# User_Interface.net
KiCad netlist of a schematic drawn in Altium Designer
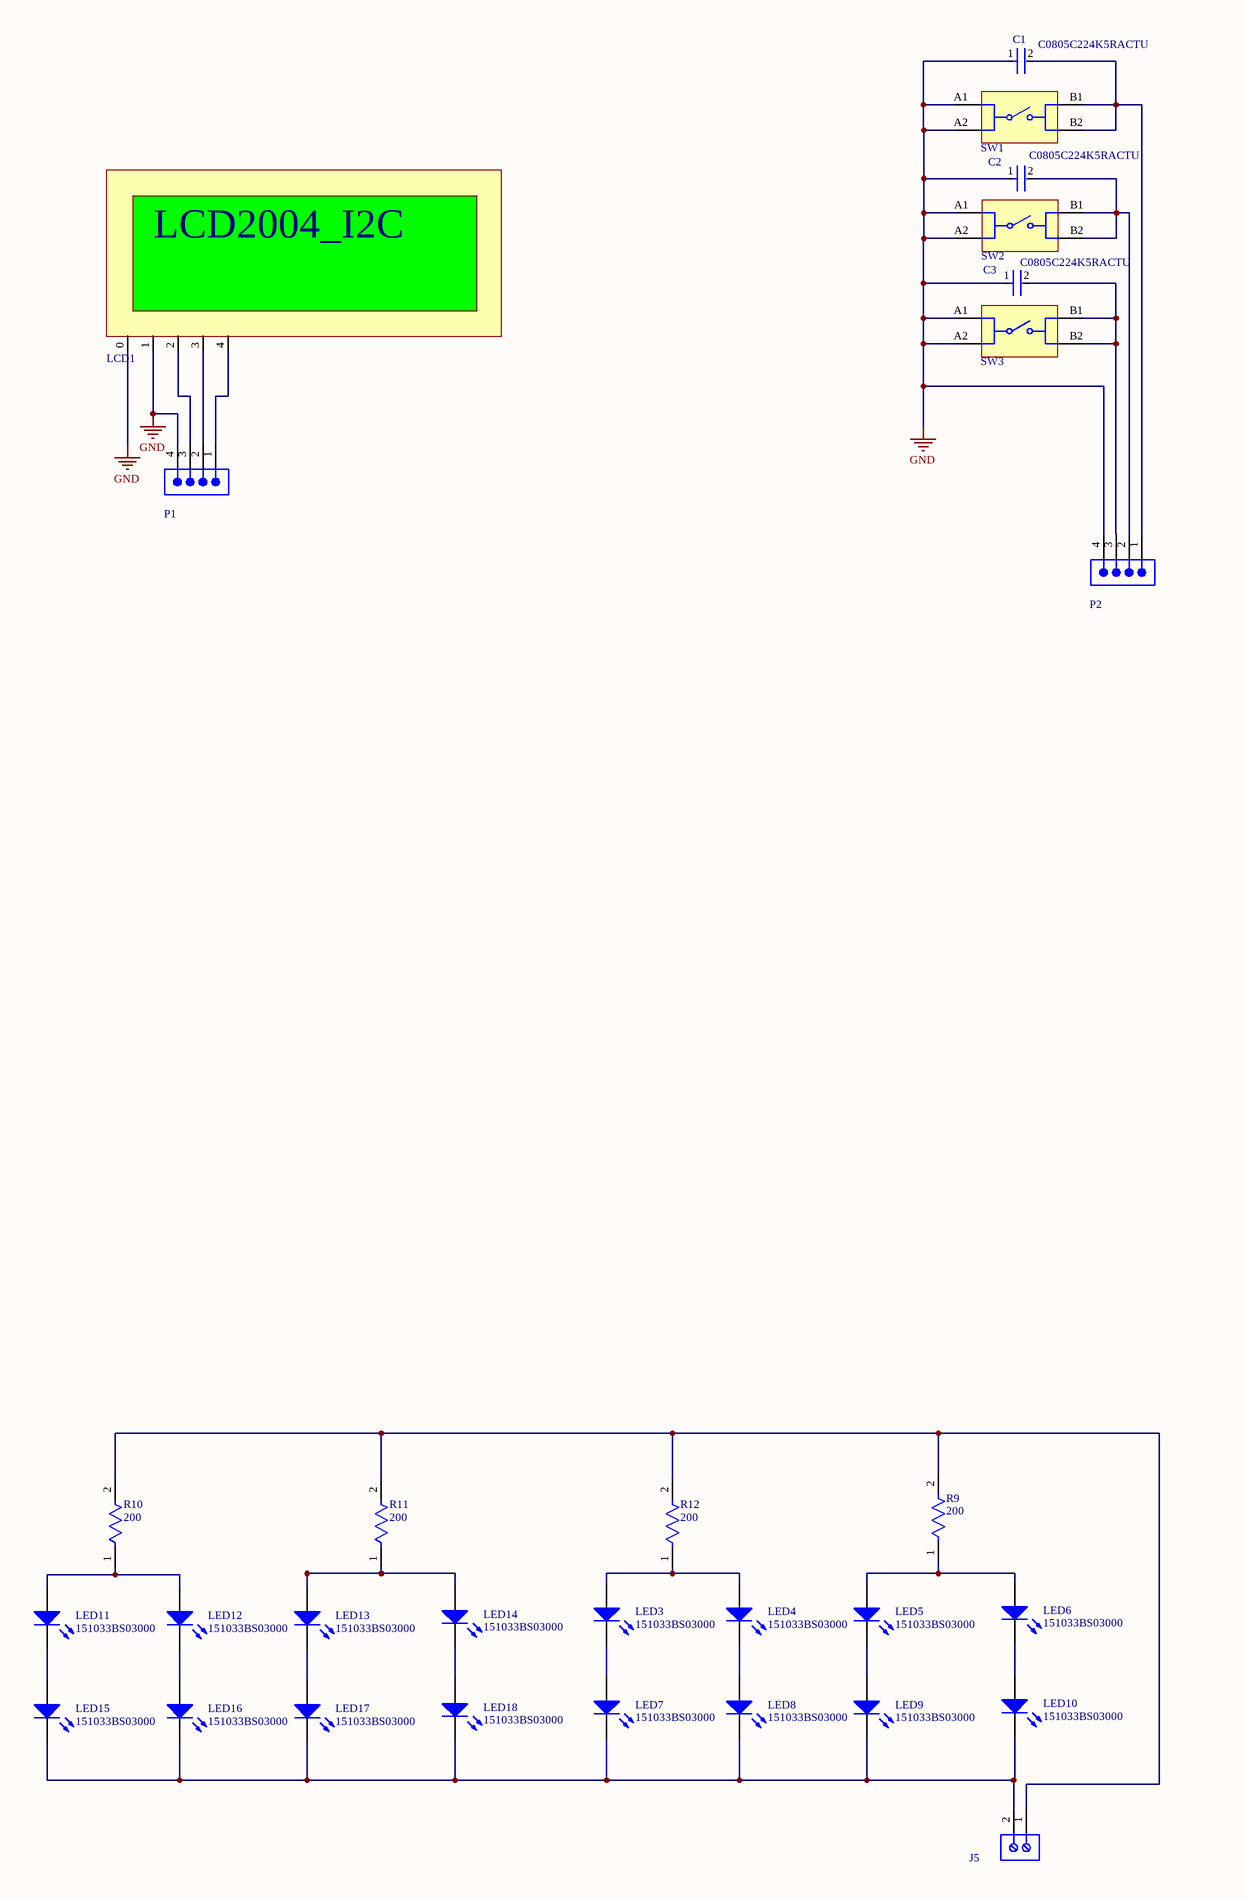
[diagram p0: User_Interface.SchDoc, left]
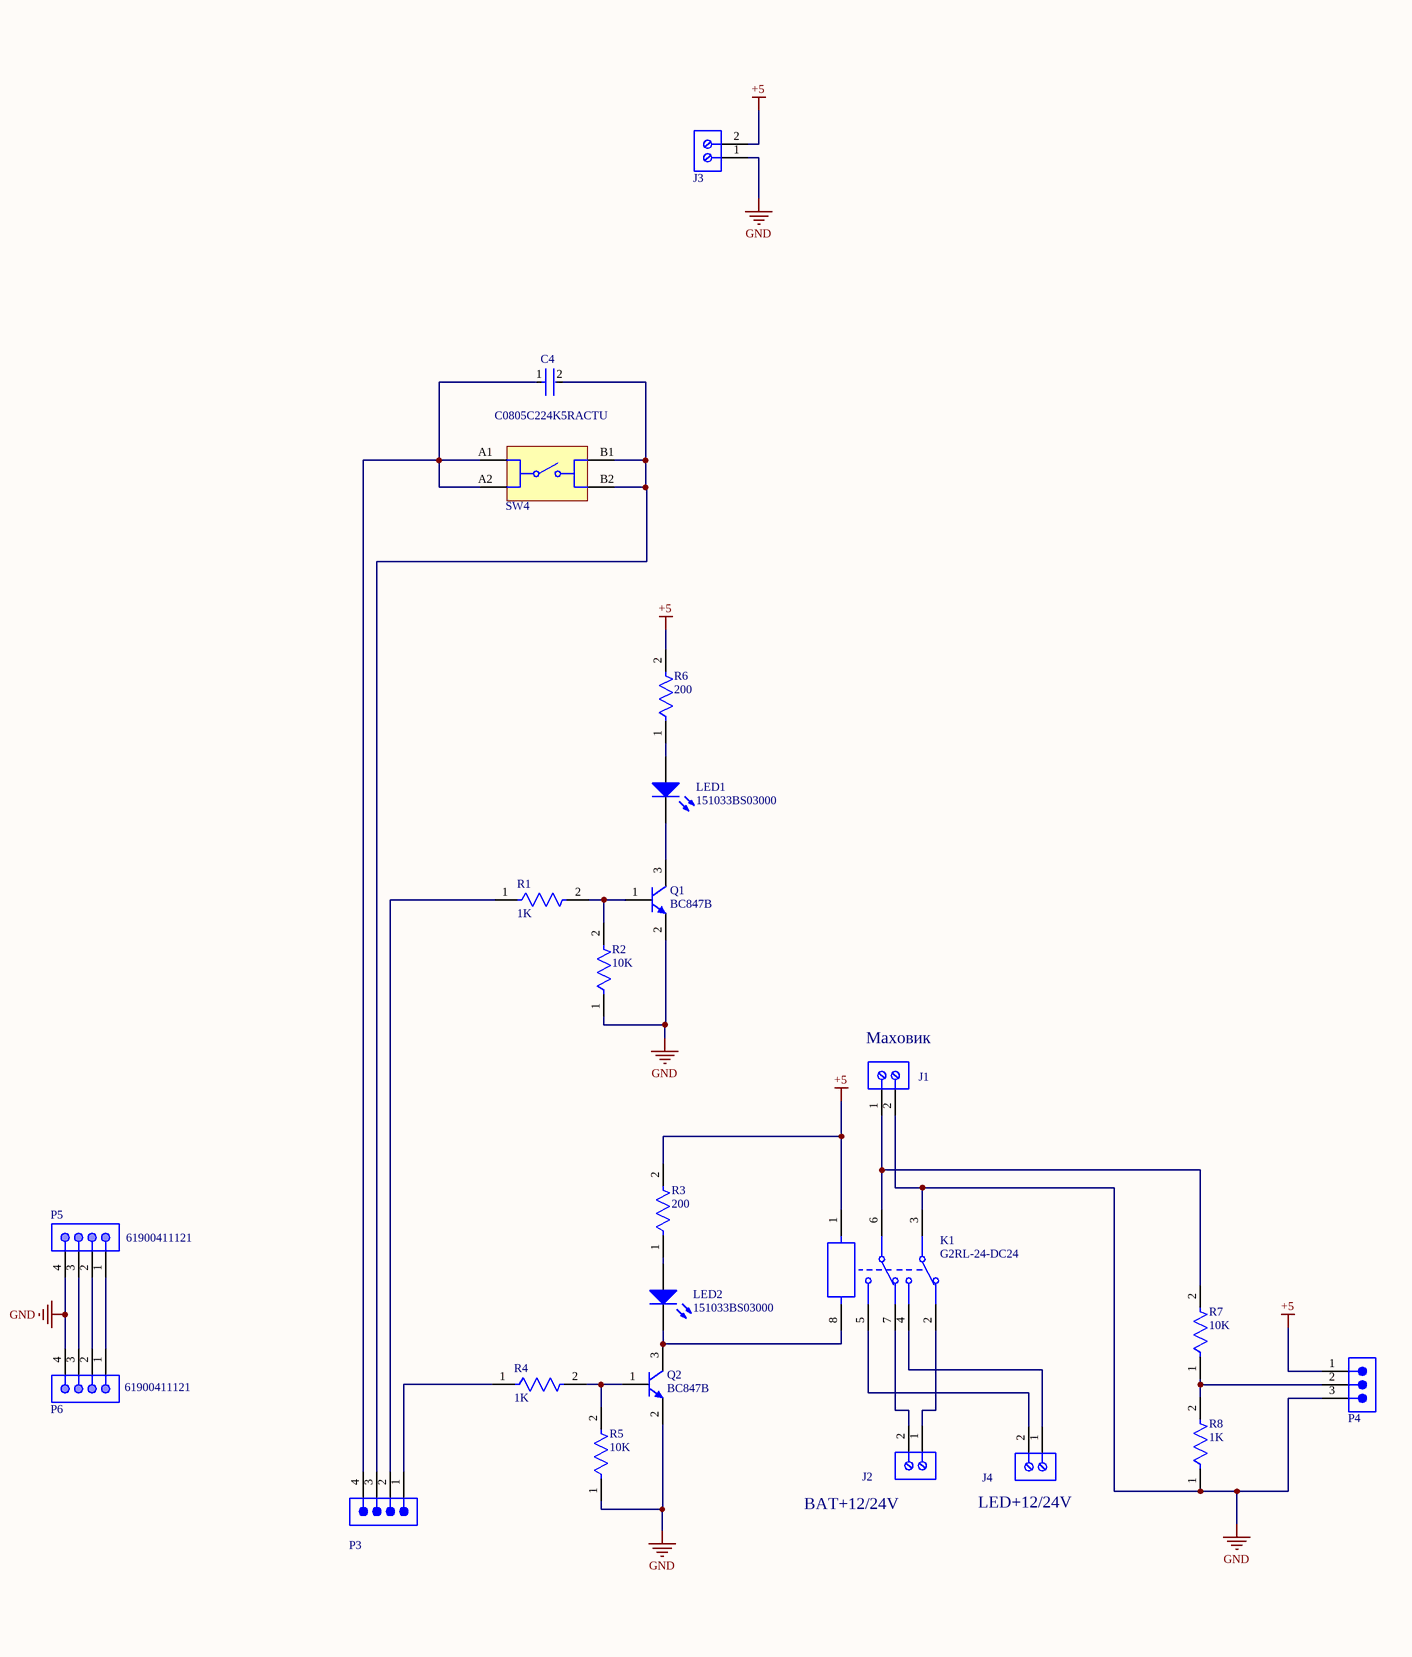
[diagram p1: User_Interface.SchDoc, right]

(export (version "E")
  (design (tool "Eeschema 10.0.6"))
  (components
    (comp (ref "C1")
      (value "C0805C224K5RACTU")
      (footprint "FP-C0805C-DN-IPC_A")
      (description "CAP CER 0.22UF 50V X7R 0805")
      (fields
        (field (name "MANUFACTURER") "KEMET")
        (field (name "OCTOPART") "https://octopart.com/c0805c224k5ractu-kemet-144670")
      )
      (libsource (lib "Pasive_components") (part "CMP-1036-04552-2"))
    )
    (comp (ref "C2")
      (value "C0805C224K5RACTU")
      (footprint "FP-C0805C-DN-IPC_A")
      (description "CAP CER 0.22UF 50V X7R 0805")
      (fields
        (field (name "MANUFACTURER") "KEMET")
        (field (name "OCTOPART") "https://octopart.com/c0805c224k5ractu-kemet-144670")
      )
      (libsource (lib "Pasive_components") (part "CMP-1036-04552-2"))
    )
    (comp (ref "C3")
      (value "C0805C224K5RACTU")
      (footprint "FP-C0805C-DN-IPC_A")
      (description "CAP CER 0.22UF 50V X7R 0805")
      (fields
        (field (name "MANUFACTURER") "KEMET")
        (field (name "OCTOPART") "https://octopart.com/c0805c224k5ractu-kemet-144670")
      )
      (libsource (lib "Pasive_components") (part "CMP-1036-04552-2"))
    )
    (comp (ref "C4")
      (value "C0805C224K5RACTU")
      (footprint "FP-C0805C-DN-IPC_A")
      (description "CAP CER 0.22UF 50V X7R 0805")
      (fields
        (field (name "MANUFACTURER") "KEMET")
        (field (name "OCTOPART") "https://octopart.com/c0805c224k5ractu-kemet-144670")
      )
      (libsource (lib "Pasive_components") (part "CMP-1036-04552-2"))
    )
    (comp (ref "J1")
      (value "691101710002")
      (footprint "691101710002")
      (description "WR-TBL Series 101 Horizontal Entry Modular, THT, pitch 5mm, 2p")
      (fields (field (name "MANUFACTURER") "Wurth Elektronik"))
      (libsource (lib "Altium_WR-TBL (rev23a)") (part "691101710002"))
    )
    (comp (ref "J2")
      (value "691101710002")
      (footprint "691101710002")
      (description "WR-TBL Series 101 Horizontal Entry Modular, THT, pitch 5mm, 2p")
      (fields (field (name "MANUFACTURER") "Wurth Elektronik"))
      (libsource (lib "Altium_WR-TBL (rev23a)") (part "691101710002"))
    )
    (comp (ref "J3")
      (value "691101710002")
      (footprint "691101710002")
      (description "WR-TBL Series 101 Horizontal Entry Modular, THT, pitch 5mm, 2p")
      (fields (field (name "MANUFACTURER") "Wurth Elektronik"))
      (libsource (lib "Altium_WR-TBL (rev23a)") (part "691101710002"))
    )
    (comp (ref "J4")
      (value "691101710002")
      (footprint "691101710002")
      (description "WR-TBL Series 101 Horizontal Entry Modular, THT, pitch 5mm, 2p")
      (fields (field (name "MANUFACTURER") "Wurth Elektronik"))
      (libsource (lib "Altium_WR-TBL (rev23a)") (part "691101710002"))
    )
    (comp (ref "J5")
      (value "691101710002")
      (footprint "691101710002")
      (description "WR-TBL Series 101 Horizontal Entry Modular, THT, pitch 5mm, 2p")
      (fields (field (name "MANUFACTURER") "Wurth Elektronik"))
      (libsource (lib "Altium_WR-TBL (rev23a)") (part "691101710002"))
    )
    (comp (ref "K1")
      (value "G2RL-24-DC24")
      (footprint "OMRON-G2RL-24_V")
      (fields (field (name "MANUFACTURER") "Omron"))
      (libsource (lib "Altium Content Vault") (part "RELAY-DPDT-8_C"))
    )
    (comp (ref "LCD1")
      (value "2004_I2C")
      (footprint "LCD2004_I2C")
      (libsource (lib "LCD2004_I2C") (part "LCD2004_I2C"))
    )
    (comp (ref "LED1")
      (value "151033BS03000")
      (footprint "Type 3mm")
      (description "THT LED round mono-color waterclear, WL-TMRW , Blue")
      (fields (field (name "MANUFACTURER") "Wuerth Elektronik"))
      (libsource (lib "Optic-LED") (part "151033BS03000"))
    )
    (comp (ref "LED2")
      (value "151033BS03000")
      (footprint "Type 3mm")
      (description "THT LED round mono-color waterclear, WL-TMRW , Blue")
      (fields (field (name "MANUFACTURER") "Wuerth Elektronik"))
      (libsource (lib "Optic-LED") (part "151033BS03000"))
    )
    (comp (ref "LED3")
      (value "151033BS03000")
      (footprint "Type 3mm")
      (description "THT LED round mono-color waterclear, WL-TMRW , Blue")
      (fields (field (name "MANUFACTURER") "Wuerth Elektronik"))
      (libsource (lib "Optic-LED") (part "151033BS03000"))
    )
    (comp (ref "LED4")
      (value "151033BS03000")
      (footprint "Type 3mm")
      (description "THT LED round mono-color waterclear, WL-TMRW , Blue")
      (fields (field (name "MANUFACTURER") "Wuerth Elektronik"))
      (libsource (lib "Optic-LED") (part "151033BS03000"))
    )
    (comp (ref "LED5")
      (value "151033BS03000")
      (footprint "Type 3mm")
      (description "THT LED round mono-color waterclear, WL-TMRW , Blue")
      (fields (field (name "MANUFACTURER") "Wuerth Elektronik"))
      (libsource (lib "Optic-LED") (part "151033BS03000"))
    )
    (comp (ref "LED6")
      (value "151033BS03000")
      (footprint "Type 3mm")
      (description "THT LED round mono-color waterclear, WL-TMRW , Blue")
      (fields (field (name "MANUFACTURER") "Wuerth Elektronik"))
      (libsource (lib "Optic-LED") (part "151033BS03000"))
    )
    (comp (ref "LED7")
      (value "151033BS03000")
      (footprint "Type 3mm")
      (description "THT LED round mono-color waterclear, WL-TMRW , Blue")
      (fields (field (name "MANUFACTURER") "Wuerth Elektronik"))
      (libsource (lib "Optic-LED") (part "151033BS03000"))
    )
    (comp (ref "LED8")
      (value "151033BS03000")
      (footprint "Type 3mm")
      (description "THT LED round mono-color waterclear, WL-TMRW , Blue")
      (fields (field (name "MANUFACTURER") "Wuerth Elektronik"))
      (libsource (lib "Optic-LED") (part "151033BS03000"))
    )
    (comp (ref "LED9")
      (value "151033BS03000")
      (footprint "Type 3mm")
      (description "THT LED round mono-color waterclear, WL-TMRW , Blue")
      (fields (field (name "MANUFACTURER") "Wuerth Elektronik"))
      (libsource (lib "Optic-LED") (part "151033BS03000"))
    )
    (comp (ref "LED10")
      (value "151033BS03000")
      (footprint "Type 3mm")
      (description "THT LED round mono-color waterclear, WL-TMRW , Blue")
      (fields (field (name "MANUFACTURER") "Wuerth Elektronik"))
      (libsource (lib "Optic-LED") (part "151033BS03000"))
    )
    (comp (ref "LED11")
      (value "151033BS03000")
      (footprint "Type 3mm")
      (description "THT LED round mono-color waterclear, WL-TMRW , Blue")
      (fields (field (name "MANUFACTURER") "Wuerth Elektronik"))
      (libsource (lib "Optic-LED") (part "151033BS03000"))
    )
    (comp (ref "LED12")
      (value "151033BS03000")
      (footprint "Type 3mm")
      (description "THT LED round mono-color waterclear, WL-TMRW , Blue")
      (fields (field (name "MANUFACTURER") "Wuerth Elektronik"))
      (libsource (lib "Optic-LED") (part "151033BS03000"))
    )
    (comp (ref "LED13")
      (value "151033BS03000")
      (footprint "Type 3mm")
      (description "THT LED round mono-color waterclear, WL-TMRW , Blue")
      (fields (field (name "MANUFACTURER") "Wuerth Elektronik"))
      (libsource (lib "Optic-LED") (part "151033BS03000"))
    )
    (comp (ref "LED14")
      (value "151033BS03000")
      (footprint "Type 3mm")
      (description "THT LED round mono-color waterclear, WL-TMRW , Blue")
      (fields (field (name "MANUFACTURER") "Wuerth Elektronik"))
      (libsource (lib "Optic-LED") (part "151033BS03000"))
    )
    (comp (ref "LED15")
      (value "151033BS03000")
      (footprint "Type 3mm")
      (description "THT LED round mono-color waterclear, WL-TMRW , Blue")
      (fields (field (name "MANUFACTURER") "Wuerth Elektronik"))
      (libsource (lib "Optic-LED") (part "151033BS03000"))
    )
    (comp (ref "LED16")
      (value "151033BS03000")
      (footprint "Type 3mm")
      (description "THT LED round mono-color waterclear, WL-TMRW , Blue")
      (fields (field (name "MANUFACTURER") "Wuerth Elektronik"))
      (libsource (lib "Optic-LED") (part "151033BS03000"))
    )
    (comp (ref "LED17")
      (value "151033BS03000")
      (footprint "Type 3mm")
      (description "THT LED round mono-color waterclear, WL-TMRW , Blue")
      (fields (field (name "MANUFACTURER") "Wuerth Elektronik"))
      (libsource (lib "Optic-LED") (part "151033BS03000"))
    )
    (comp (ref "LED18")
      (value "151033BS03000")
      (footprint "Type 3mm")
      (description "THT LED round mono-color waterclear, WL-TMRW , Blue")
      (fields (field (name "MANUFACTURER") "Wuerth Elektronik"))
      (libsource (lib "Optic-LED") (part "151033BS03000"))
    )
    (comp (ref "P1")
      (value "61900411121")
      (footprint "61900411121")
      (description "WR-WTB THT Male Vertical Locking Header, pitch 2.54mm, 4pins")
      (fields (field (name "MANUFACTURER") "Wurth Elektronik"))
      (libsource (lib "Altium_WR-WTB (rev22b)") (part "61900411121"))
    )
    (comp (ref "P2")
      (value "61900411121")
      (footprint "61900411121")
      (description "WR-WTB THT Male Vertical Locking Header, pitch 2.54mm, 4pins")
      (fields (field (name "MANUFACTURER") "Wurth Elektronik"))
      (libsource (lib "Altium_WR-WTB (rev22b)") (part "61900411121"))
    )
    (comp (ref "P3")
      (value "61900411121")
      (footprint "61900411121")
      (description "WR-WTB THT Male Vertical Locking Header, pitch 2.54mm, 4pins")
      (fields (field (name "MANUFACTURER") "Wurth Elektronik"))
      (libsource (lib "Altium_WR-WTB (rev22b)") (part "61900411121"))
    )
    (comp (ref "P4")
      (value "61900311121")
      (footprint "61900311121")
      (description "WR-WTB THT Male Vertical Locking Header, pitch 2.54mm, 3pins")
      (fields (field (name "MANUFACTURER") "Wurth Elektronik"))
      (libsource (lib "Altium_WR-WTB (rev22b)") (part "61900311121"))
    )
    (comp (ref "P5")
      (value "61900411121")
      (footprint "61900411121")
      (description "WR-WTB THT Male Vertical Locking Header, pitch 2.54mm, 4p")
      (fields (field (name "PUBLISHER") "Wurth Elektronik"))
      (libsource (lib "Altium_WR-WTB (rev20a)") (part "61900411121"))
    )
    (comp (ref "P6")
      (value "61900411121")
      (footprint "61900411121")
      (description "WR-WTB THT Male Vertical Locking Header, pitch 2.54mm, 4p")
      (fields (field (name "PUBLISHER") "Wurth Elektronik"))
      (libsource (lib "Altium_WR-WTB (rev20a)") (part "61900411121"))
    )
    (comp (ref "Q1")
      (value "BC847B")
      (footprint "INF-SOT23_M")
      (description "NPN Silicon AF Transistor, 45 V VCEO, 100 mA IC, SOT23, Reel, Green")
      (fields (field (name "MANUFACTURER") "Infineon"))
      (libsource (lib "Altium Content Vault") (part "INF-BJTNPN-BEC-3"))
    )
    (comp (ref "Q2")
      (value "BC847B")
      (footprint "INF-SOT23_M")
      (description "NPN Silicon AF Transistor, 45 V VCEO, 100 mA IC, SOT23, Reel, Green")
      (fields (field (name "MANUFACTURER") "Infineon"))
      (libsource (lib "Altium Content Vault") (part "INF-BJTNPN-BEC-3"))
    )
    (comp (ref "R1")
      (value "1K")
      (footprint "FP-CRCW0805-e3-MFG")
      (description "RES Thick Film, 10kΩ, 1%, 0.125W, 100ppm/°C, 0805")
      (fields (field (name "TOLERANCE") "1%"))
      (libsource (lib "Pasive_components") (part "CMP-2001-04908-2"))
    )
    (comp (ref "R2")
      (value "10K")
      (footprint "FP-CRCW0805-e3-MFG")
      (description "RES Thick Film, 10kΩ, 1%, 0.125W, 100ppm/°C, 0805")
      (fields (field (name "TOLERANCE") "1%"))
      (libsource (lib "Pasive_components") (part "CMP-2001-04908-2"))
    )
    (comp (ref "R3")
      (value "200")
      (footprint "FP-CRCW0805-e3-MFG")
      (description "RES Thick Film, 200Ω, 1%, 0.125W, 100ppm/°C, 0805")
      (fields (field (name "TOLERANCE") "1%"))
      (libsource (lib "Pasive_components") (part "CMP-2001-04908-2"))
    )
    (comp (ref "R4")
      (value "1K")
      (footprint "FP-CRCW0805-e3-MFG")
      (description "RES Thick Film, 1kΩ, 1%, 0.125W, 100ppm/°C, 0805")
      (fields (field (name "TOLERANCE") "1%"))
      (libsource (lib "Pasive_components") (part "CMP-2001-04908-2"))
    )
    (comp (ref "R5")
      (value "10K")
      (footprint "FP-CRCW0805-e3-MFG")
      (description "RES Thick Film, 10kΩ, 1%, 0.125W, 100ppm/°C, 0805")
      (fields (field (name "TOLERANCE") "1%"))
      (libsource (lib "Pasive_components") (part "CMP-2001-04908-2"))
    )
    (comp (ref "R6")
      (value "200")
      (footprint "FP-CRCW0805-e3-MFG")
      (description "RES Thick Film, 200Ω, 1%, 0.125W, 100ppm/°C, 0805")
      (fields (field (name "TOLERANCE") "1%"))
      (libsource (lib "Pasive_components") (part "CMP-2001-04908-2"))
    )
    (comp (ref "R7")
      (value "10K")
      (footprint "FP-CRCW0805-e3-MFG")
      (description "RES Thick Film, 10kΩ, 1%, 0.125W, 100ppm/°C, 0805")
      (fields (field (name "TOLERANCE") "1%"))
      (libsource (lib "Pasive_components") (part "CMP-2001-04908-2"))
    )
    (comp (ref "R8")
      (value "1K")
      (footprint "FP-CRCW0805-e3-MFG")
      (description "RES Thick Film, 1kΩ, 1%, 0.125W, 100ppm/°C, 0805")
      (fields (field (name "TOLERANCE") "1%"))
      (libsource (lib "Pasive_components") (part "CMP-2001-04908-2"))
    )
    (comp (ref "R9")
      (value "200")
      (footprint "FP-CRCW0805-e3-MFG")
      (description "RES Thick Film, 200Ω, 1%, 0.125W, 100ppm/°C, 0805")
      (fields (field (name "TOLERANCE") "1%"))
      (libsource (lib "Pasive_components") (part "CMP-2001-04908-2"))
    )
    (comp (ref "R10")
      (value "200")
      (footprint "FP-CRCW0805-e3-MFG")
      (description "RES Thick Film, 200Ω, 1%, 0.125W, 100ppm/°C, 0805")
      (fields (field (name "TOLERANCE") "1%"))
      (libsource (lib "Pasive_components") (part "CMP-2001-04908-2"))
    )
    (comp (ref "R11")
      (value "200")
      (footprint "FP-CRCW0805-e3-MFG")
      (description "RES Thick Film, 200Ω, 1%, 0.125W, 100ppm/°C, 0805")
      (fields (field (name "TOLERANCE") "1%"))
      (libsource (lib "Pasive_components") (part "CMP-2001-04908-2"))
    )
    (comp (ref "R12")
      (value "200")
      (footprint "FP-CRCW0805-e3-MFG")
      (description "RES Thick Film, 200Ω, 1%, 0.125W, 100ppm/°C, 0805")
      (fields (field (name "TOLERANCE") "1%"))
      (libsource (lib "Pasive_components") (part "CMP-2001-04908-2"))
    )
    (comp (ref "SW1")
      (value "430156043726")
      (footprint "4301x60437x6")
      (description "WS-TATV THT Tact Switch 6x6mm, SPST-NO, 12VDC, 50mA, 260g")
      (fields (field (name "MANUFACTURER") "Wurth Elektronik"))
      (libsource (lib "Altium_WS-TATV (rev22a)") (part "430156043726"))
    )
    (comp (ref "SW2")
      (value "430156043726")
      (footprint "4301x60437x6")
      (description "WS-TATV THT Tact Switch 6x6mm, SPST-NO, 12VDC, 50mA, 260g")
      (fields (field (name "MANUFACTURER") "Wurth Elektronik"))
      (libsource (lib "Altium_WS-TATV (rev22a)") (part "430156043726"))
    )
    (comp (ref "SW3")
      (value "430156043726")
      (footprint "4301x60437x6")
      (description "WS-TATV THT Tact Switch 6x6mm, SPST-NO, 12VDC, 50mA, 260g")
      (fields (field (name "MANUFACTURER") "Wurth Elektronik"))
      (libsource (lib "Altium_WS-TATV (rev22a)") (part "430156043726"))
    )
    (comp (ref "SW4")
      (value "430156043726")
      (footprint "4301x60437x6")
      (description "WS-TATV THT Tact Switch 6x6mm, SPST-NO, 12VDC, 50mA, 260g")
      (fields (field (name "MANUFACTURER") "Wurth Elektronik"))
      (libsource (lib "Altium_WS-TATV (rev22a)") (part "430156043726"))
    )
  )
  (nets
    (net (code "1") (name "+5") (class "Default")
      (node (ref "J3") (pin "2") (pinfunction "2_2") (pintype "passive"))
      (node (ref "K1") (pin "1") (pinfunction "1_1") (pintype "passive"))
      (node (ref "P4") (pin "1") (pinfunction "1_1") (pintype "passive"))
      (node (ref "R3") (pin "2") (pinfunction "2_2") (pintype "passive"))
      (node (ref "R6") (pin "2") (pinfunction "2_2") (pintype "passive"))
    )
    (net (code "2") (name "GND") (class "Default")
      (node (ref "C1") (pin "1") (pinfunction "1_1") (pintype "passive"))
      (node (ref "C2") (pin "1") (pinfunction "1_1") (pintype "passive"))
      (node (ref "C3") (pin "1") (pinfunction "1_1") (pintype "passive"))
      (node (ref "J1") (pin "2") (pinfunction "2_2") (pintype "passive"))
      (node (ref "J3") (pin "1") (pinfunction "1_1") (pintype "passive"))
      (node (ref "K1") (pin "3") (pinfunction "3_3") (pintype "passive"))
      (node (ref "LCD1") (pin "0") (pinfunction "0_0") (pintype "passive"))
      (node (ref "LCD1") (pin "1") (pinfunction "1_1") (pintype "passive"))
      (node (ref "P1") (pin "4") (pinfunction "4_4") (pintype "passive"))
      (node (ref "P2") (pin "4") (pinfunction "4_4") (pintype "passive"))
      (node (ref "P4") (pin "3") (pinfunction "3_3") (pintype "passive"))
      (node (ref "P5") (pin "4") (pinfunction "4_4") (pintype "passive"))
      (node (ref "P6") (pin "4") (pinfunction "4_4") (pintype "passive"))
      (node (ref "Q1") (pin "2") (pinfunction "E_2") (pintype "passive"))
      (node (ref "Q2") (pin "2") (pinfunction "E_2") (pintype "passive"))
      (node (ref "R2") (pin "1") (pinfunction "1_1") (pintype "passive"))
      (node (ref "R5") (pin "1") (pinfunction "1_1") (pintype "passive"))
      (node (ref "R8") (pin "1") (pinfunction "1_1") (pintype "passive"))
      (node (ref "SW1") (pin "A1") (pinfunction "A1_A1") (pintype "passive"))
      (node (ref "SW1") (pin "A2") (pinfunction "A2_A2") (pintype "passive"))
      (node (ref "SW2") (pin "A1") (pinfunction "A1_A1") (pintype "passive"))
      (node (ref "SW2") (pin "A2") (pinfunction "A2_A2") (pintype "passive"))
      (node (ref "SW3") (pin "A1") (pinfunction "A1_A1") (pintype "passive"))
      (node (ref "SW3") (pin "A2") (pinfunction "A2_A2") (pintype "passive"))
    )
    (net (code "3") (name "Net-(C1-Pad2)") (class "Default")
      (node (ref "C1") (pin "2") (pinfunction "2_2") (pintype "passive"))
      (node (ref "P2") (pin "1") (pinfunction "1_1") (pintype "passive"))
      (node (ref "SW1") (pin "B1") (pinfunction "B1_B1") (pintype "passive"))
      (node (ref "SW1") (pin "B2") (pinfunction "B2_B2") (pintype "passive"))
    )
    (net (code "4") (name "Net-(C2-Pad2)") (class "Default")
      (node (ref "C2") (pin "2") (pinfunction "2_2") (pintype "passive"))
      (node (ref "P2") (pin "2") (pinfunction "2_2") (pintype "passive"))
      (node (ref "SW2") (pin "B1") (pinfunction "B1_B1") (pintype "passive"))
      (node (ref "SW2") (pin "B2") (pinfunction "B2_B2") (pintype "passive"))
    )
    (net (code "5") (name "Net-(C3-Pad2)") (class "Default")
      (node (ref "C3") (pin "2") (pinfunction "2_2") (pintype "passive"))
      (node (ref "P2") (pin "3") (pinfunction "3_3") (pintype "passive"))
      (node (ref "SW3") (pin "B1") (pinfunction "B1_B1") (pintype "passive"))
      (node (ref "SW3") (pin "B2") (pinfunction "B2_B2") (pintype "passive"))
    )
    (net (code "6") (name "Net-(C4-Pad1)") (class "Default")
      (node (ref "C4") (pin "1") (pinfunction "1_1") (pintype "passive"))
      (node (ref "P3") (pin "4") (pinfunction "4_4") (pintype "passive"))
      (node (ref "SW4") (pin "A1") (pinfunction "A1_A1") (pintype "passive"))
      (node (ref "SW4") (pin "A2") (pinfunction "A2_A2") (pintype "passive"))
    )
    (net (code "7") (name "Net-(C4-Pad2)") (class "Default")
      (node (ref "C4") (pin "2") (pinfunction "2_2") (pintype "passive"))
      (node (ref "P3") (pin "3") (pinfunction "3_3") (pintype "passive"))
      (node (ref "SW4") (pin "B1") (pinfunction "B1_B1") (pintype "passive"))
      (node (ref "SW4") (pin "B2") (pinfunction "B2_B2") (pintype "passive"))
    )
    (net (code "8") (name "Net-(J1-Pad1)") (class "Default")
      (node (ref "J1") (pin "1") (pinfunction "1_1") (pintype "passive"))
      (node (ref "K1") (pin "6") (pinfunction "6_6") (pintype "passive"))
      (node (ref "R7") (pin "2") (pinfunction "2_2") (pintype "passive"))
    )
    (net (code "9") (name "Net-(J2-Pad1)") (class "Default")
      (node (ref "J2") (pin "1") (pinfunction "1_1") (pintype "passive"))
      (node (ref "K1") (pin "2") (pinfunction "2_2") (pintype "passive"))
    )
    (net (code "10") (name "Net-(J2-Pad2)") (class "Default")
      (node (ref "J2") (pin "2") (pinfunction "2_2") (pintype "passive"))
      (node (ref "K1") (pin "7") (pinfunction "7_7") (pintype "passive"))
    )
    (net (code "11") (name "Net-(J4-Pad1)") (class "Default")
      (node (ref "J4") (pin "1") (pinfunction "1_1") (pintype "passive"))
      (node (ref "K1") (pin "4") (pinfunction "4_4") (pintype "passive"))
    )
    (net (code "12") (name "Net-(J4-Pad2)") (class "Default")
      (node (ref "J4") (pin "2") (pinfunction "2_2") (pintype "passive"))
      (node (ref "K1") (pin "5") (pinfunction "5_5") (pintype "passive"))
    )
    (net (code "13") (name "Net-(J5-Pad1)") (class "Default")
      (node (ref "J5") (pin "1") (pinfunction "1_1") (pintype "passive"))
      (node (ref "R10") (pin "2") (pinfunction "2_2") (pintype "passive"))
      (node (ref "R11") (pin "2") (pinfunction "2_2") (pintype "passive"))
      (node (ref "R12") (pin "2") (pinfunction "2_2") (pintype "passive"))
      (node (ref "R9") (pin "2") (pinfunction "2_2") (pintype "passive"))
    )
    (net (code "14") (name "Net-(LCD1-Pad2)") (class "Default")
      (node (ref "LCD1") (pin "2") (pinfunction "2_2") (pintype "passive"))
      (node (ref "P1") (pin "3") (pinfunction "3_3") (pintype "passive"))
    )
    (net (code "15") (name "Net-(LCD1-Pad3)") (class "Default")
      (node (ref "LCD1") (pin "3") (pinfunction "3_3") (pintype "passive"))
      (node (ref "P1") (pin "2") (pinfunction "2_2") (pintype "passive"))
    )
    (net (code "16") (name "Net-(LCD1-Pad4)") (class "Default")
      (node (ref "LCD1") (pin "4") (pinfunction "4_4") (pintype "passive"))
      (node (ref "P1") (pin "1") (pinfunction "1_1") (pintype "passive"))
    )
    (net (code "17") (name "Net-(LED1-A)") (class "Default")
      (node (ref "LED1") (pin "2") (pinfunction "A_2") (pintype "passive"))
      (node (ref "R6") (pin "1") (pinfunction "1_1") (pintype "passive"))
    )
    (net (code "18") (name "Net-(LED1-K)") (class "Default")
      (node (ref "LED1") (pin "1") (pinfunction "K_1") (pintype "passive"))
      (node (ref "Q1") (pin "3") (pinfunction "C_3") (pintype "passive"))
    )
    (net (code "19") (name "Net-(LED2-A)") (class "Default")
      (node (ref "LED2") (pin "2") (pinfunction "A_2") (pintype "passive"))
      (node (ref "R3") (pin "1") (pinfunction "1_1") (pintype "passive"))
    )
    (net (code "20") (name "Net-(LED2-K)") (class "Default")
      (node (ref "K1") (pin "8") (pinfunction "8_8") (pintype "passive"))
      (node (ref "LED2") (pin "1") (pinfunction "K_1") (pintype "passive"))
      (node (ref "Q2") (pin "3") (pinfunction "C_3") (pintype "passive"))
    )
    (net (code "21") (name "Net-(LED3-A)") (class "Default")
      (node (ref "LED3") (pin "2") (pinfunction "A_2") (pintype "passive"))
      (node (ref "LED4") (pin "2") (pinfunction "A_2") (pintype "passive"))
      (node (ref "R12") (pin "1") (pinfunction "1_1") (pintype "passive"))
    )
    (net (code "22") (name "Net-(LED3-K)") (class "Default")
      (node (ref "LED3") (pin "1") (pinfunction "K_1") (pintype "passive"))
      (node (ref "LED7") (pin "2") (pinfunction "A_2") (pintype "passive"))
    )
    (net (code "23") (name "Net-(LED4-K)") (class "Default")
      (node (ref "LED4") (pin "1") (pinfunction "K_1") (pintype "passive"))
      (node (ref "LED8") (pin "2") (pinfunction "A_2") (pintype "passive"))
    )
    (net (code "24") (name "Net-(LED5-A)") (class "Default")
      (node (ref "LED5") (pin "2") (pinfunction "A_2") (pintype "passive"))
      (node (ref "LED6") (pin "2") (pinfunction "A_2") (pintype "passive"))
      (node (ref "R9") (pin "1") (pinfunction "1_1") (pintype "passive"))
    )
    (net (code "25") (name "Net-(LED5-K)") (class "Default")
      (node (ref "LED5") (pin "1") (pinfunction "K_1") (pintype "passive"))
      (node (ref "LED9") (pin "2") (pinfunction "A_2") (pintype "passive"))
    )
    (net (code "26") (name "Net-(LED10-A)") (class "Default")
      (node (ref "LED10") (pin "2") (pinfunction "A_2") (pintype "passive"))
      (node (ref "LED6") (pin "1") (pinfunction "K_1") (pintype "passive"))
    )
    (net (code "27") (name "Net-(LED10-K)") (class "Default")
      (node (ref "J5") (pin "2") (pinfunction "2_2") (pintype "passive"))
      (node (ref "LED10") (pin "1") (pinfunction "K_1") (pintype "passive"))
      (node (ref "LED15") (pin "1") (pinfunction "K_1") (pintype "passive"))
      (node (ref "LED16") (pin "1") (pinfunction "K_1") (pintype "passive"))
      (node (ref "LED17") (pin "1") (pinfunction "K_1") (pintype "passive"))
      (node (ref "LED18") (pin "1") (pinfunction "K_1") (pintype "passive"))
      (node (ref "LED7") (pin "1") (pinfunction "K_1") (pintype "passive"))
      (node (ref "LED8") (pin "1") (pinfunction "K_1") (pintype "passive"))
      (node (ref "LED9") (pin "1") (pinfunction "K_1") (pintype "passive"))
    )
    (net (code "28") (name "Net-(LED11-A)") (class "Default")
      (node (ref "LED11") (pin "2") (pinfunction "A_2") (pintype "passive"))
      (node (ref "LED12") (pin "2") (pinfunction "A_2") (pintype "passive"))
      (node (ref "R10") (pin "1") (pinfunction "1_1") (pintype "passive"))
    )
    (net (code "29") (name "Net-(LED11-K)") (class "Default")
      (node (ref "LED11") (pin "1") (pinfunction "K_1") (pintype "passive"))
      (node (ref "LED15") (pin "2") (pinfunction "A_2") (pintype "passive"))
    )
    (net (code "30") (name "Net-(LED12-K)") (class "Default")
      (node (ref "LED12") (pin "1") (pinfunction "K_1") (pintype "passive"))
      (node (ref "LED16") (pin "2") (pinfunction "A_2") (pintype "passive"))
    )
    (net (code "31") (name "Net-(LED13-A)") (class "Default")
      (node (ref "LED13") (pin "2") (pinfunction "A_2") (pintype "passive"))
      (node (ref "LED14") (pin "2") (pinfunction "A_2") (pintype "passive"))
      (node (ref "R11") (pin "1") (pinfunction "1_1") (pintype "passive"))
    )
    (net (code "32") (name "Net-(LED13-K)") (class "Default")
      (node (ref "LED13") (pin "1") (pinfunction "K_1") (pintype "passive"))
      (node (ref "LED17") (pin "2") (pinfunction "A_2") (pintype "passive"))
    )
    (net (code "33") (name "Net-(LED14-K)") (class "Default")
      (node (ref "LED14") (pin "1") (pinfunction "K_1") (pintype "passive"))
      (node (ref "LED18") (pin "2") (pinfunction "A_2") (pintype "passive"))
    )
    (net (code "34") (name "Net-(P3-Pad1)") (class "Default")
      (node (ref "P3") (pin "1") (pinfunction "1_1") (pintype "passive"))
      (node (ref "R4") (pin "1") (pinfunction "1_1") (pintype "passive"))
    )
    (net (code "35") (name "Net-(P3-Pad2)") (class "Default")
      (node (ref "P3") (pin "2") (pinfunction "2_2") (pintype "passive"))
      (node (ref "R1") (pin "1") (pinfunction "1_1") (pintype "passive"))
    )
    (net (code "36") (name "Net-(P4-Pad2)") (class "Default")
      (node (ref "P4") (pin "2") (pinfunction "2_2") (pintype "passive"))
      (node (ref "R7") (pin "1") (pinfunction "1_1") (pintype "passive"))
      (node (ref "R8") (pin "2") (pinfunction "2_2") (pintype "passive"))
    )
    (net (code "37") (name "Net-(P5-Pad1)") (class "Default")
      (node (ref "P5") (pin "1") (pinfunction "1_1") (pintype "passive"))
      (node (ref "P6") (pin "1") (pinfunction "1_1") (pintype "passive"))
    )
    (net (code "38") (name "Net-(P5-Pad2)") (class "Default")
      (node (ref "P5") (pin "2") (pinfunction "2_2") (pintype "passive"))
      (node (ref "P6") (pin "2") (pinfunction "2_2") (pintype "passive"))
    )
    (net (code "39") (name "Net-(P5-Pad3)") (class "Default")
      (node (ref "P5") (pin "3") (pinfunction "3_3") (pintype "passive"))
      (node (ref "P6") (pin "3") (pinfunction "3_3") (pintype "passive"))
    )
    (net (code "40") (name "Net-(Q1-B)") (class "Default")
      (node (ref "Q1") (pin "1") (pinfunction "B_1") (pintype "passive"))
      (node (ref "R1") (pin "2") (pinfunction "2_2") (pintype "passive"))
      (node (ref "R2") (pin "2") (pinfunction "2_2") (pintype "passive"))
    )
    (net (code "41") (name "Net-(Q2-B)") (class "Default")
      (node (ref "Q2") (pin "1") (pinfunction "B_1") (pintype "passive"))
      (node (ref "R4") (pin "2") (pinfunction "2_2") (pintype "passive"))
      (node (ref "R5") (pin "2") (pinfunction "2_2") (pintype "passive"))
    )
  )
)
